# CONNECT.net
KiCad netlist of a schematic drawn in Altium Designer
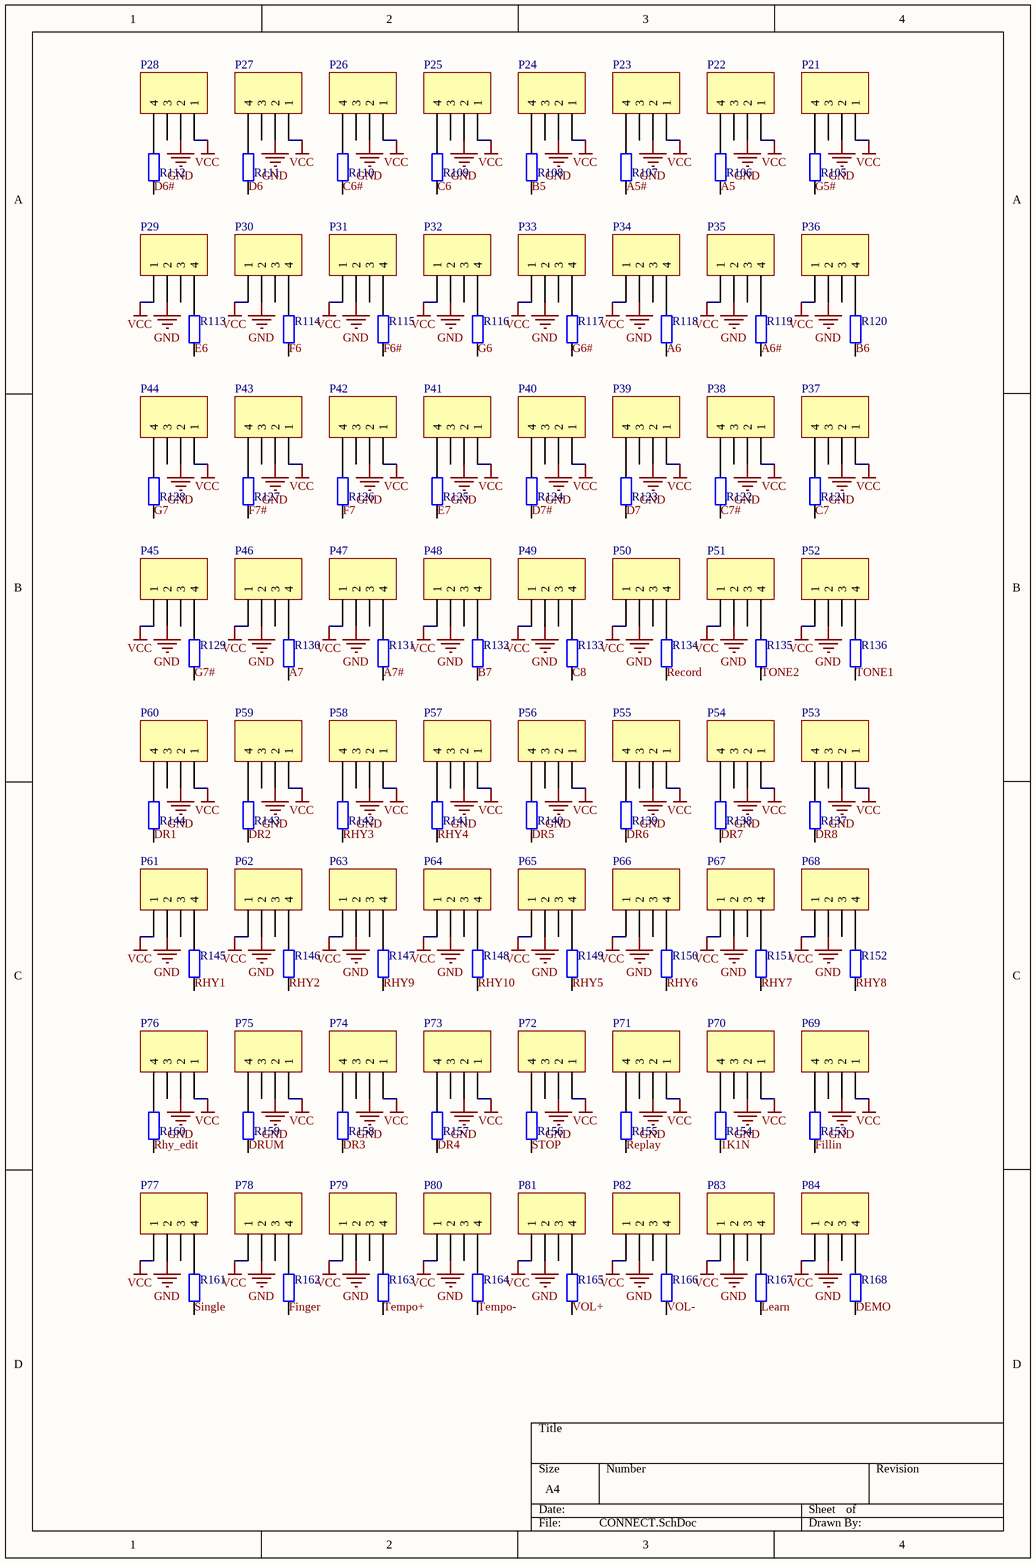
[diagram p0: CONNECT.SchDoc]

(export (version "E")
  (design (tool "Eeschema 10.0.6"))
  (components
    (comp (ref "P21")
      (value "Header 4")
      (footprint "FPC1.0-2H-WS-4P")
      (description "Header, 4-Pin")
      (fields (field (name "PUBLISHER") "Altium Limited"))
      (libsource (lib "") (part "Header 4_1"))
    )
    (comp (ref "P22")
      (value "Header 4")
      (footprint "FPC1.0-2H-WS-4P")
      (description "Header, 4-Pin")
      (fields (field (name "PUBLISHER") "Altium Limited"))
      (libsource (lib "") (part "Header 4_1"))
    )
    (comp (ref "P23")
      (value "Header 4")
      (footprint "FPC1.0-2H-WS-4P")
      (description "Header, 4-Pin")
      (fields (field (name "PUBLISHER") "Altium Limited"))
      (libsource (lib "") (part "Header 4_1"))
    )
    (comp (ref "P24")
      (value "Header 4")
      (footprint "FPC1.0-2H-WS-4P")
      (description "Header, 4-Pin")
      (fields (field (name "PUBLISHER") "Altium Limited"))
      (libsource (lib "") (part "Header 4_1"))
    )
    (comp (ref "P25")
      (value "Header 4")
      (footprint "FPC1.0-2H-WS-4P")
      (description "Header, 4-Pin")
      (fields (field (name "PUBLISHER") "Altium Limited"))
      (libsource (lib "") (part "Header 4_1"))
    )
    (comp (ref "P26")
      (value "Header 4")
      (footprint "FPC1.0-2H-WS-4P")
      (description "Header, 4-Pin")
      (fields (field (name "PUBLISHER") "Altium Limited"))
      (libsource (lib "") (part "Header 4_1"))
    )
    (comp (ref "P27")
      (value "Header 4")
      (footprint "FPC1.0-2H-WS-4P")
      (description "Header, 4-Pin")
      (fields (field (name "PUBLISHER") "Altium Limited"))
      (libsource (lib "") (part "Header 4_1"))
    )
    (comp (ref "P28")
      (value "Header 4")
      (footprint "FPC1.0-2H-WS-4P")
      (description "Header, 4-Pin")
      (fields (field (name "PUBLISHER") "Altium Limited"))
      (libsource (lib "") (part "Header 4_1"))
    )
    (comp (ref "P29")
      (value "Header 4")
      (footprint "FPC1.0-2H-WS-4P")
      (description "Header, 4-Pin")
      (fields (field (name "PUBLISHER") "Altium Limited"))
      (libsource (lib "Miscellaneous Connectors") (part "Header 4"))
    )
    (comp (ref "P30")
      (value "Header 4")
      (footprint "FPC1.0-2H-WS-4P")
      (description "Header, 4-Pin")
      (fields (field (name "PUBLISHER") "Altium Limited"))
      (libsource (lib "Miscellaneous Connectors") (part "Header 4"))
    )
    (comp (ref "P31")
      (value "Header 4")
      (footprint "FPC1.0-2H-WS-4P")
      (description "Header, 4-Pin")
      (fields (field (name "PUBLISHER") "Altium Limited"))
      (libsource (lib "Miscellaneous Connectors") (part "Header 4"))
    )
    (comp (ref "P32")
      (value "Header 4")
      (footprint "FPC1.0-2H-WS-4P")
      (description "Header, 4-Pin")
      (fields (field (name "PUBLISHER") "Altium Limited"))
      (libsource (lib "Miscellaneous Connectors") (part "Header 4"))
    )
    (comp (ref "P33")
      (value "Header 4")
      (footprint "FPC1.0-2H-WS-4P")
      (description "Header, 4-Pin")
      (fields (field (name "PUBLISHER") "Altium Limited"))
      (libsource (lib "Miscellaneous Connectors") (part "Header 4"))
    )
    (comp (ref "P34")
      (value "Header 4")
      (footprint "FPC1.0-2H-WS-4P")
      (description "Header, 4-Pin")
      (fields (field (name "PUBLISHER") "Altium Limited"))
      (libsource (lib "Miscellaneous Connectors") (part "Header 4"))
    )
    (comp (ref "P35")
      (value "Header 4")
      (footprint "FPC1.0-2H-WS-4P")
      (description "Header, 4-Pin")
      (fields (field (name "PUBLISHER") "Altium Limited"))
      (libsource (lib "Miscellaneous Connectors") (part "Header 4"))
    )
    (comp (ref "P36")
      (value "Header 4")
      (footprint "FPC1.0-2H-WS-4P")
      (description "Header, 4-Pin")
      (fields (field (name "PUBLISHER") "Altium Limited"))
      (libsource (lib "Miscellaneous Connectors") (part "Header 4"))
    )
    (comp (ref "P37")
      (value "Header 4")
      (footprint "FPC1.0-2H-WS-4P")
      (description "Header, 4-Pin")
      (fields (field (name "PUBLISHER") "Altium Limited"))
      (libsource (lib "") (part "Header 4_1"))
    )
    (comp (ref "P38")
      (value "Header 4")
      (footprint "FPC1.0-2H-WS-4P")
      (description "Header, 4-Pin")
      (fields (field (name "PUBLISHER") "Altium Limited"))
      (libsource (lib "") (part "Header 4_1"))
    )
    (comp (ref "P39")
      (value "Header 4")
      (footprint "FPC1.0-2H-WS-4P")
      (description "Header, 4-Pin")
      (fields (field (name "PUBLISHER") "Altium Limited"))
      (libsource (lib "") (part "Header 4_1"))
    )
    (comp (ref "P40")
      (value "Header 4")
      (footprint "FPC1.0-2H-WS-4P")
      (description "Header, 4-Pin")
      (fields (field (name "PUBLISHER") "Altium Limited"))
      (libsource (lib "") (part "Header 4_1"))
    )
    (comp (ref "P41")
      (value "Header 4")
      (footprint "FPC1.0-2H-WS-4P")
      (description "Header, 4-Pin")
      (fields (field (name "PUBLISHER") "Altium Limited"))
      (libsource (lib "") (part "Header 4_1"))
    )
    (comp (ref "P42")
      (value "Header 4")
      (footprint "FPC1.0-2H-WS-4P")
      (description "Header, 4-Pin")
      (fields (field (name "PUBLISHER") "Altium Limited"))
      (libsource (lib "") (part "Header 4_1"))
    )
    (comp (ref "P43")
      (value "Header 4")
      (footprint "FPC1.0-2H-WS-4P")
      (description "Header, 4-Pin")
      (fields (field (name "PUBLISHER") "Altium Limited"))
      (libsource (lib "") (part "Header 4_1"))
    )
    (comp (ref "P44")
      (value "Header 4")
      (footprint "FPC1.0-2H-WS-4P")
      (description "Header, 4-Pin")
      (fields (field (name "PUBLISHER") "Altium Limited"))
      (libsource (lib "") (part "Header 4_1"))
    )
    (comp (ref "P45")
      (value "Header 4")
      (footprint "FPC1.0-2H-WS-4P")
      (description "Header, 4-Pin")
      (fields (field (name "PUBLISHER") "Altium Limited"))
      (libsource (lib "Miscellaneous Connectors") (part "Header 4"))
    )
    (comp (ref "P46")
      (value "Header 4")
      (footprint "FPC1.0-2H-WS-4P")
      (description "Header, 4-Pin")
      (fields (field (name "PUBLISHER") "Altium Limited"))
      (libsource (lib "Miscellaneous Connectors") (part "Header 4"))
    )
    (comp (ref "P47")
      (value "Header 4")
      (footprint "FPC1.0-2H-WS-4P")
      (description "Header, 4-Pin")
      (fields (field (name "PUBLISHER") "Altium Limited"))
      (libsource (lib "Miscellaneous Connectors") (part "Header 4"))
    )
    (comp (ref "P48")
      (value "Header 4")
      (footprint "FPC1.0-2H-WS-4P")
      (description "Header, 4-Pin")
      (fields (field (name "PUBLISHER") "Altium Limited"))
      (libsource (lib "Miscellaneous Connectors") (part "Header 4"))
    )
    (comp (ref "P49")
      (value "Header 4")
      (footprint "FPC1.0-2H-WS-4P")
      (description "Header, 4-Pin")
      (fields (field (name "PUBLISHER") "Altium Limited"))
      (libsource (lib "Miscellaneous Connectors") (part "Header 4"))
    )
    (comp (ref "P50")
      (value "Header 4")
      (footprint "FPC1.0-2H-WS-4P")
      (description "Header, 4-Pin")
      (fields (field (name "PUBLISHER") "Altium Limited"))
      (libsource (lib "Miscellaneous Connectors") (part "Header 4"))
    )
    (comp (ref "P51")
      (value "Header 4")
      (footprint "FPC1.0-2H-WS-4P")
      (description "Header, 4-Pin")
      (fields (field (name "PUBLISHER") "Altium Limited"))
      (libsource (lib "Miscellaneous Connectors") (part "Header 4"))
    )
    (comp (ref "P52")
      (value "Header 4")
      (footprint "FPC1.0-2H-WS-4P")
      (description "Header, 4-Pin")
      (fields (field (name "PUBLISHER") "Altium Limited"))
      (libsource (lib "Miscellaneous Connectors") (part "Header 4"))
    )
    (comp (ref "P53")
      (value "Header 4")
      (footprint "FPC1.0-2H-WS-4P")
      (description "Header, 4-Pin")
      (fields (field (name "PUBLISHER") "Altium Limited"))
      (libsource (lib "") (part "Header 4_1"))
    )
    (comp (ref "P54")
      (value "Header 4")
      (footprint "FPC1.0-2H-WS-4P")
      (description "Header, 4-Pin")
      (fields (field (name "PUBLISHER") "Altium Limited"))
      (libsource (lib "") (part "Header 4_1"))
    )
    (comp (ref "P55")
      (value "Header 4")
      (footprint "FPC1.0-2H-WS-4P")
      (description "Header, 4-Pin")
      (fields (field (name "PUBLISHER") "Altium Limited"))
      (libsource (lib "") (part "Header 4_1"))
    )
    (comp (ref "P56")
      (value "Header 4")
      (footprint "FPC1.0-2H-WS-4P")
      (description "Header, 4-Pin")
      (fields (field (name "PUBLISHER") "Altium Limited"))
      (libsource (lib "") (part "Header 4_1"))
    )
    (comp (ref "P57")
      (value "Header 4")
      (footprint "FPC1.0-2H-WS-4P")
      (description "Header, 4-Pin")
      (fields (field (name "PUBLISHER") "Altium Limited"))
      (libsource (lib "") (part "Header 4_1"))
    )
    (comp (ref "P58")
      (value "Header 4")
      (footprint "FPC1.0-2H-WS-4P")
      (description "Header, 4-Pin")
      (fields (field (name "PUBLISHER") "Altium Limited"))
      (libsource (lib "") (part "Header 4_1"))
    )
    (comp (ref "P59")
      (value "Header 4")
      (footprint "FPC1.0-2H-WS-4P")
      (description "Header, 4-Pin")
      (fields (field (name "PUBLISHER") "Altium Limited"))
      (libsource (lib "") (part "Header 4_1"))
    )
    (comp (ref "P60")
      (value "Header 4")
      (footprint "FPC1.0-2H-WS-4P")
      (description "Header, 4-Pin")
      (fields (field (name "PUBLISHER") "Altium Limited"))
      (libsource (lib "") (part "Header 4_1"))
    )
    (comp (ref "P61")
      (value "Header 4")
      (footprint "FPC1.0-2H-WS-4P")
      (description "Header, 4-Pin")
      (fields (field (name "PUBLISHER") "Altium Limited"))
      (libsource (lib "Miscellaneous Connectors") (part "Header 4"))
    )
    (comp (ref "P62")
      (value "Header 4")
      (footprint "FPC1.0-2H-WS-4P")
      (description "Header, 4-Pin")
      (fields (field (name "PUBLISHER") "Altium Limited"))
      (libsource (lib "Miscellaneous Connectors") (part "Header 4"))
    )
    (comp (ref "P63")
      (value "Header 4")
      (footprint "FPC1.0-2H-WS-4P")
      (description "Header, 4-Pin")
      (fields (field (name "PUBLISHER") "Altium Limited"))
      (libsource (lib "Miscellaneous Connectors") (part "Header 4"))
    )
    (comp (ref "P64")
      (value "Header 4")
      (footprint "FPC1.0-2H-WS-4P")
      (description "Header, 4-Pin")
      (fields (field (name "PUBLISHER") "Altium Limited"))
      (libsource (lib "Miscellaneous Connectors") (part "Header 4"))
    )
    (comp (ref "P65")
      (value "Header 4")
      (footprint "FPC1.0-2H-WS-4P")
      (description "Header, 4-Pin")
      (fields (field (name "PUBLISHER") "Altium Limited"))
      (libsource (lib "Miscellaneous Connectors") (part "Header 4"))
    )
    (comp (ref "P66")
      (value "Header 4")
      (footprint "FPC1.0-2H-WS-4P")
      (description "Header, 4-Pin")
      (fields (field (name "PUBLISHER") "Altium Limited"))
      (libsource (lib "Miscellaneous Connectors") (part "Header 4"))
    )
    (comp (ref "P67")
      (value "Header 4")
      (footprint "FPC1.0-2H-WS-4P")
      (description "Header, 4-Pin")
      (fields (field (name "PUBLISHER") "Altium Limited"))
      (libsource (lib "Miscellaneous Connectors") (part "Header 4"))
    )
    (comp (ref "P68")
      (value "Header 4")
      (footprint "FPC1.0-2H-WS-4P")
      (description "Header, 4-Pin")
      (fields (field (name "PUBLISHER") "Altium Limited"))
      (libsource (lib "Miscellaneous Connectors") (part "Header 4"))
    )
    (comp (ref "P69")
      (value "Header 4")
      (footprint "FPC1.0-2H-WS-4P")
      (description "Header, 4-Pin")
      (fields (field (name "PUBLISHER") "Altium Limited"))
      (libsource (lib "") (part "Header 4_1"))
    )
    (comp (ref "P70")
      (value "Header 4")
      (footprint "FPC1.0-2H-WS-4P")
      (description "Header, 4-Pin")
      (fields (field (name "PUBLISHER") "Altium Limited"))
      (libsource (lib "") (part "Header 4_1"))
    )
    (comp (ref "P71")
      (value "Header 4")
      (footprint "FPC1.0-2H-WS-4P")
      (description "Header, 4-Pin")
      (fields (field (name "PUBLISHER") "Altium Limited"))
      (libsource (lib "") (part "Header 4_1"))
    )
    (comp (ref "P72")
      (value "Header 4")
      (footprint "FPC1.0-2H-WS-4P")
      (description "Header, 4-Pin")
      (fields (field (name "PUBLISHER") "Altium Limited"))
      (libsource (lib "") (part "Header 4_1"))
    )
    (comp (ref "P73")
      (value "Header 4")
      (footprint "FPC1.0-2H-WS-4P")
      (description "Header, 4-Pin")
      (fields (field (name "PUBLISHER") "Altium Limited"))
      (libsource (lib "") (part "Header 4_1"))
    )
    (comp (ref "P74")
      (value "Header 4")
      (footprint "FPC1.0-2H-WS-4P")
      (description "Header, 4-Pin")
      (fields (field (name "PUBLISHER") "Altium Limited"))
      (libsource (lib "") (part "Header 4_1"))
    )
    (comp (ref "P75")
      (value "Header 4")
      (footprint "FPC1.0-2H-WS-4P")
      (description "Header, 4-Pin")
      (fields (field (name "PUBLISHER") "Altium Limited"))
      (libsource (lib "") (part "Header 4_1"))
    )
    (comp (ref "P76")
      (value "Header 4")
      (footprint "FPC1.0-2H-WS-4P")
      (description "Header, 4-Pin")
      (fields (field (name "PUBLISHER") "Altium Limited"))
      (libsource (lib "") (part "Header 4_1"))
    )
    (comp (ref "P77")
      (value "Header 4")
      (footprint "FPC1.0-2H-WS-4P")
      (description "Header, 4-Pin")
      (fields (field (name "PUBLISHER") "Altium Limited"))
      (libsource (lib "Miscellaneous Connectors") (part "Header 4"))
    )
    (comp (ref "P78")
      (value "Header 4")
      (footprint "FPC1.0-2H-WS-4P")
      (description "Header, 4-Pin")
      (fields (field (name "PUBLISHER") "Altium Limited"))
      (libsource (lib "Miscellaneous Connectors") (part "Header 4"))
    )
    (comp (ref "P79")
      (value "Header 4")
      (footprint "FPC1.0-2H-WS-4P")
      (description "Header, 4-Pin")
      (fields (field (name "PUBLISHER") "Altium Limited"))
      (libsource (lib "Miscellaneous Connectors") (part "Header 4"))
    )
    (comp (ref "P80")
      (value "Header 4")
      (footprint "FPC1.0-2H-WS-4P")
      (description "Header, 4-Pin")
      (fields (field (name "PUBLISHER") "Altium Limited"))
      (libsource (lib "Miscellaneous Connectors") (part "Header 4"))
    )
    (comp (ref "P81")
      (value "Header 4")
      (footprint "FPC1.0-2H-WS-4P")
      (description "Header, 4-Pin")
      (fields (field (name "PUBLISHER") "Altium Limited"))
      (libsource (lib "Miscellaneous Connectors") (part "Header 4"))
    )
    (comp (ref "P82")
      (value "Header 4")
      (footprint "FPC1.0-2H-WS-4P")
      (description "Header, 4-Pin")
      (fields (field (name "PUBLISHER") "Altium Limited"))
      (libsource (lib "Miscellaneous Connectors") (part "Header 4"))
    )
    (comp (ref "P83")
      (value "Header 4")
      (footprint "FPC1.0-2H-WS-4P")
      (description "Header, 4-Pin")
      (fields (field (name "PUBLISHER") "Altium Limited"))
      (libsource (lib "Miscellaneous Connectors") (part "Header 4"))
    )
    (comp (ref "P84")
      (value "Header 4")
      (footprint "FPC1.0-2H-WS-4P")
      (description "Header, 4-Pin")
      (fields (field (name "PUBLISHER") "Altium Limited"))
      (libsource (lib "Miscellaneous Connectors") (part "Header 4"))
    )
    (comp (ref "R105")
      (value "1KΩ (1001) ±1%")
      (footprint "0603_R")
      (description "贴片电阻")
      (libsource (lib "Miscellaneous Devices LC") (part "0603 1KΩ (1001) 1%"))
    )
    (comp (ref "R106")
      (value "1KΩ (1001) ±1%")
      (footprint "0603_R")
      (description "贴片电阻")
      (libsource (lib "Miscellaneous Devices LC") (part "0603 1KΩ (1001) 1%"))
    )
    (comp (ref "R107")
      (value "1KΩ (1001) ±1%")
      (footprint "0603_R")
      (description "贴片电阻")
      (libsource (lib "Miscellaneous Devices LC") (part "0603 1KΩ (1001) 1%"))
    )
    (comp (ref "R108")
      (value "1KΩ (1001) ±1%")
      (footprint "0603_R")
      (description "贴片电阻")
      (libsource (lib "Miscellaneous Devices LC") (part "0603 1KΩ (1001) 1%"))
    )
    (comp (ref "R109")
      (value "1KΩ (1001) ±1%")
      (footprint "0603_R")
      (description "贴片电阻")
      (libsource (lib "Miscellaneous Devices LC") (part "0603 1KΩ (1001) 1%"))
    )
    (comp (ref "R110")
      (value "1KΩ (1001) ±1%")
      (footprint "0603_R")
      (description "贴片电阻")
      (libsource (lib "Miscellaneous Devices LC") (part "0603 1KΩ (1001) 1%"))
    )
    (comp (ref "R111")
      (value "1KΩ (1001) ±1%")
      (footprint "0603_R")
      (description "贴片电阻")
      (libsource (lib "Miscellaneous Devices LC") (part "0603 1KΩ (1001) 1%"))
    )
    (comp (ref "R112")
      (value "1KΩ (1001) ±1%")
      (footprint "0603_R")
      (description "贴片电阻")
      (libsource (lib "Miscellaneous Devices LC") (part "0603 1KΩ (1001) 1%"))
    )
    (comp (ref "R113")
      (value "1KΩ (1001) ±1%")
      (footprint "0603_R")
      (description "贴片电阻")
      (libsource (lib "") (part "0603 1KΩ (1001) 1%_1"))
    )
    (comp (ref "R114")
      (value "1KΩ (1001) ±1%")
      (footprint "0603_R")
      (description "贴片电阻")
      (libsource (lib "") (part "0603 1KΩ (1001) 1%_1"))
    )
    (comp (ref "R115")
      (value "1KΩ (1001) ±1%")
      (footprint "0603_R")
      (description "贴片电阻")
      (libsource (lib "") (part "0603 1KΩ (1001) 1%_1"))
    )
    (comp (ref "R116")
      (value "1KΩ (1001) ±1%")
      (footprint "0603_R")
      (description "贴片电阻")
      (libsource (lib "") (part "0603 1KΩ (1001) 1%_1"))
    )
    (comp (ref "R117")
      (value "1KΩ (1001) ±1%")
      (footprint "0603_R")
      (description "贴片电阻")
      (libsource (lib "") (part "0603 1KΩ (1001) 1%_1"))
    )
    (comp (ref "R118")
      (value "1KΩ (1001) ±1%")
      (footprint "0603_R")
      (description "贴片电阻")
      (libsource (lib "") (part "0603 1KΩ (1001) 1%_1"))
    )
    (comp (ref "R119")
      (value "1KΩ (1001) ±1%")
      (footprint "0603_R")
      (description "贴片电阻")
      (libsource (lib "") (part "0603 1KΩ (1001) 1%_1"))
    )
    (comp (ref "R120")
      (value "1KΩ (1001) ±1%")
      (footprint "0603_R")
      (description "贴片电阻")
      (libsource (lib "") (part "0603 1KΩ (1001) 1%_1"))
    )
    (comp (ref "R121")
      (value "1KΩ (1001) ±1%")
      (footprint "0603_R")
      (description "贴片电阻")
      (libsource (lib "Miscellaneous Devices LC") (part "0603 1KΩ (1001) 1%"))
    )
    (comp (ref "R122")
      (value "1KΩ (1001) ±1%")
      (footprint "0603_R")
      (description "贴片电阻")
      (libsource (lib "Miscellaneous Devices LC") (part "0603 1KΩ (1001) 1%"))
    )
    (comp (ref "R123")
      (value "1KΩ (1001) ±1%")
      (footprint "0603_R")
      (description "贴片电阻")
      (libsource (lib "Miscellaneous Devices LC") (part "0603 1KΩ (1001) 1%"))
    )
    (comp (ref "R124")
      (value "1KΩ (1001) ±1%")
      (footprint "0603_R")
      (description "贴片电阻")
      (libsource (lib "Miscellaneous Devices LC") (part "0603 1KΩ (1001) 1%"))
    )
    (comp (ref "R125")
      (value "1KΩ (1001) ±1%")
      (footprint "0603_R")
      (description "贴片电阻")
      (libsource (lib "Miscellaneous Devices LC") (part "0603 1KΩ (1001) 1%"))
    )
    (comp (ref "R126")
      (value "1KΩ (1001) ±1%")
      (footprint "0603_R")
      (description "贴片电阻")
      (libsource (lib "Miscellaneous Devices LC") (part "0603 1KΩ (1001) 1%"))
    )
    (comp (ref "R127")
      (value "1KΩ (1001) ±1%")
      (footprint "0603_R")
      (description "贴片电阻")
      (libsource (lib "Miscellaneous Devices LC") (part "0603 1KΩ (1001) 1%"))
    )
    (comp (ref "R128")
      (value "1KΩ (1001) ±1%")
      (footprint "0603_R")
      (description "贴片电阻")
      (libsource (lib "Miscellaneous Devices LC") (part "0603 1KΩ (1001) 1%"))
    )
    (comp (ref "R129")
      (value "1KΩ (1001) ±1%")
      (footprint "0603_R")
      (description "贴片电阻")
      (libsource (lib "") (part "0603 1KΩ (1001) 1%_1"))
    )
    (comp (ref "R130")
      (value "1KΩ (1001) ±1%")
      (footprint "0603_R")
      (description "贴片电阻")
      (libsource (lib "") (part "0603 1KΩ (1001) 1%_1"))
    )
    (comp (ref "R131")
      (value "1KΩ (1001) ±1%")
      (footprint "0603_R")
      (description "贴片电阻")
      (libsource (lib "") (part "0603 1KΩ (1001) 1%_1"))
    )
    (comp (ref "R132")
      (value "1KΩ (1001) ±1%")
      (footprint "0603_R")
      (description "贴片电阻")
      (libsource (lib "") (part "0603 1KΩ (1001) 1%_1"))
    )
    (comp (ref "R133")
      (value "1KΩ (1001) ±1%")
      (footprint "0603_R")
      (description "贴片电阻")
      (libsource (lib "") (part "0603 1KΩ (1001) 1%_1"))
    )
    (comp (ref "R134")
      (value "1KΩ (1001) ±1%")
      (footprint "0603_R")
      (description "贴片电阻")
      (libsource (lib "") (part "0603 1KΩ (1001) 1%_1"))
    )
    (comp (ref "R135")
      (value "1KΩ (1001) ±1%")
      (footprint "0603_R")
      (description "贴片电阻")
      (libsource (lib "") (part "0603 1KΩ (1001) 1%_1"))
    )
    (comp (ref "R136")
      (value "1KΩ (1001) ±1%")
      (footprint "0603_R")
      (description "贴片电阻")
      (libsource (lib "") (part "0603 1KΩ (1001) 1%_1"))
    )
    (comp (ref "R137")
      (value "1KΩ (1001) ±1%")
      (footprint "0603_R")
      (description "贴片电阻")
      (libsource (lib "Miscellaneous Devices LC") (part "0603 1KΩ (1001) 1%"))
    )
    (comp (ref "R138")
      (value "1KΩ (1001) ±1%")
      (footprint "0603_R")
      (description "贴片电阻")
      (libsource (lib "Miscellaneous Devices LC") (part "0603 1KΩ (1001) 1%"))
    )
    (comp (ref "R139")
      (value "1KΩ (1001) ±1%")
      (footprint "0603_R")
      (description "贴片电阻")
      (libsource (lib "Miscellaneous Devices LC") (part "0603 1KΩ (1001) 1%"))
    )
    (comp (ref "R140")
      (value "1KΩ (1001) ±1%")
      (footprint "0603_R")
      (description "贴片电阻")
      (libsource (lib "Miscellaneous Devices LC") (part "0603 1KΩ (1001) 1%"))
    )
    (comp (ref "R141")
      (value "1KΩ (1001) ±1%")
      (footprint "0603_R")
      (description "贴片电阻")
      (libsource (lib "Miscellaneous Devices LC") (part "0603 1KΩ (1001) 1%"))
    )
    (comp (ref "R142")
      (value "1KΩ (1001) ±1%")
      (footprint "0603_R")
      (description "贴片电阻")
      (libsource (lib "Miscellaneous Devices LC") (part "0603 1KΩ (1001) 1%"))
    )
    (comp (ref "R143")
      (value "1KΩ (1001) ±1%")
      (footprint "0603_R")
      (description "贴片电阻")
      (libsource (lib "Miscellaneous Devices LC") (part "0603 1KΩ (1001) 1%"))
    )
    (comp (ref "R144")
      (value "1KΩ (1001) ±1%")
      (footprint "0603_R")
      (description "贴片电阻")
      (libsource (lib "Miscellaneous Devices LC") (part "0603 1KΩ (1001) 1%"))
    )
    (comp (ref "R145")
      (value "1KΩ (1001) ±1%")
      (footprint "0603_R")
      (description "贴片电阻")
      (libsource (lib "") (part "0603 1KΩ (1001) 1%_1"))
    )
    (comp (ref "R146")
      (value "1KΩ (1001) ±1%")
      (footprint "0603_R")
      (description "贴片电阻")
      (libsource (lib "") (part "0603 1KΩ (1001) 1%_1"))
    )
    (comp (ref "R147")
      (value "1KΩ (1001) ±1%")
      (footprint "0603_R")
      (description "贴片电阻")
      (libsource (lib "") (part "0603 1KΩ (1001) 1%_1"))
    )
    (comp (ref "R148")
      (value "1KΩ (1001) ±1%")
      (footprint "0603_R")
      (description "贴片电阻")
      (libsource (lib "") (part "0603 1KΩ (1001) 1%_1"))
    )
    (comp (ref "R149")
      (value "1KΩ (1001) ±1%")
      (footprint "0603_R")
      (description "贴片电阻")
      (libsource (lib "") (part "0603 1KΩ (1001) 1%_1"))
    )
    (comp (ref "R150")
      (value "1KΩ (1001) ±1%")
      (footprint "0603_R")
      (description "贴片电阻")
      (libsource (lib "") (part "0603 1KΩ (1001) 1%_1"))
    )
    (comp (ref "R151")
      (value "1KΩ (1001) ±1%")
      (footprint "0603_R")
      (description "贴片电阻")
      (libsource (lib "") (part "0603 1KΩ (1001) 1%_1"))
    )
    (comp (ref "R152")
      (value "1KΩ (1001) ±1%")
      (footprint "0603_R")
      (description "贴片电阻")
      (libsource (lib "") (part "0603 1KΩ (1001) 1%_1"))
    )
    (comp (ref "R153")
      (value "1KΩ (1001) ±1%")
      (footprint "0603_R")
      (description "贴片电阻")
      (libsource (lib "Miscellaneous Devices LC") (part "0603 1KΩ (1001) 1%"))
    )
    (comp (ref "R154")
      (value "1KΩ (1001) ±1%")
      (footprint "0603_R")
      (description "贴片电阻")
      (libsource (lib "Miscellaneous Devices LC") (part "0603 1KΩ (1001) 1%"))
    )
    (comp (ref "R155")
      (value "1KΩ (1001) ±1%")
      (footprint "0603_R")
      (description "贴片电阻")
      (libsource (lib "Miscellaneous Devices LC") (part "0603 1KΩ (1001) 1%"))
    )
    (comp (ref "R156")
      (value "1KΩ (1001) ±1%")
      (footprint "0603_R")
      (description "贴片电阻")
      (libsource (lib "Miscellaneous Devices LC") (part "0603 1KΩ (1001) 1%"))
    )
    (comp (ref "R157")
      (value "1KΩ (1001) ±1%")
      (footprint "0603_R")
      (description "贴片电阻")
      (libsource (lib "Miscellaneous Devices LC") (part "0603 1KΩ (1001) 1%"))
    )
    (comp (ref "R158")
      (value "1KΩ (1001) ±1%")
      (footprint "0603_R")
      (description "贴片电阻")
      (libsource (lib "Miscellaneous Devices LC") (part "0603 1KΩ (1001) 1%"))
    )
    (comp (ref "R159")
      (value "1KΩ (1001) ±1%")
      (footprint "0603_R")
      (description "贴片电阻")
      (libsource (lib "Miscellaneous Devices LC") (part "0603 1KΩ (1001) 1%"))
    )
    (comp (ref "R160")
      (value "1KΩ (1001) ±1%")
      (footprint "0603_R")
      (description "贴片电阻")
      (libsource (lib "Miscellaneous Devices LC") (part "0603 1KΩ (1001) 1%"))
    )
    (comp (ref "R161")
      (value "1KΩ (1001) ±1%")
      (footprint "0603_R")
      (description "贴片电阻")
      (libsource (lib "") (part "0603 1KΩ (1001) 1%_1"))
    )
    (comp (ref "R162")
      (value "1KΩ (1001) ±1%")
      (footprint "0603_R")
      (description "贴片电阻")
      (libsource (lib "") (part "0603 1KΩ (1001) 1%_1"))
    )
    (comp (ref "R163")
      (value "1KΩ (1001) ±1%")
      (footprint "0603_R")
      (description "贴片电阻")
      (libsource (lib "") (part "0603 1KΩ (1001) 1%_1"))
    )
    (comp (ref "R164")
      (value "1KΩ (1001) ±1%")
      (footprint "0603_R")
      (description "贴片电阻")
      (libsource (lib "") (part "0603 1KΩ (1001) 1%_1"))
    )
    (comp (ref "R165")
      (value "1KΩ (1001) ±1%")
      (footprint "0603_R")
      (description "贴片电阻")
      (libsource (lib "") (part "0603 1KΩ (1001) 1%_1"))
    )
    (comp (ref "R166")
      (value "1KΩ (1001) ±1%")
      (footprint "0603_R")
      (description "贴片电阻")
      (libsource (lib "") (part "0603 1KΩ (1001) 1%_1"))
    )
    (comp (ref "R167")
      (value "1KΩ (1001) ±1%")
      (footprint "0603_R")
      (description "贴片电阻")
      (libsource (lib "") (part "0603 1KΩ (1001) 1%_1"))
    )
    (comp (ref "R168")
      (value "1KΩ (1001) ±1%")
      (footprint "0603_R")
      (description "贴片电阻")
      (libsource (lib "") (part "0603 1KΩ (1001) 1%_1"))
    )
  )
  (nets
    (net (code "1") (name "/1K1N") (class "Default")
      (node (ref "R154") (pin "1") (pinfunction "1_1") (pintype "passive"))
    )
    (net (code "2") (name "/A5") (class "Default")
      (node (ref "R106") (pin "1") (pinfunction "1_1") (pintype "passive"))
    )
    (net (code "3") (name "/A5#") (class "Default")
      (node (ref "R107") (pin "1") (pinfunction "1_1") (pintype "passive"))
    )
    (net (code "4") (name "/A6") (class "Default")
      (node (ref "R118") (pin "1") (pinfunction "1_1") (pintype "passive"))
    )
    (net (code "5") (name "/A6#") (class "Default")
      (node (ref "R119") (pin "1") (pinfunction "1_1") (pintype "passive"))
    )
    (net (code "6") (name "/A7") (class "Default")
      (node (ref "R130") (pin "1") (pinfunction "1_1") (pintype "passive"))
    )
    (net (code "7") (name "/A7#") (class "Default")
      (node (ref "R131") (pin "1") (pinfunction "1_1") (pintype "passive"))
    )
    (net (code "8") (name "/B5") (class "Default")
      (node (ref "R108") (pin "1") (pinfunction "1_1") (pintype "passive"))
    )
    (net (code "9") (name "/B6") (class "Default")
      (node (ref "R120") (pin "1") (pinfunction "1_1") (pintype "passive"))
    )
    (net (code "10") (name "/B7") (class "Default")
      (node (ref "R132") (pin "1") (pinfunction "1_1") (pintype "passive"))
    )
    (net (code "11") (name "/C6") (class "Default")
      (node (ref "R109") (pin "1") (pinfunction "1_1") (pintype "passive"))
    )
    (net (code "12") (name "/C6#") (class "Default")
      (node (ref "R110") (pin "1") (pinfunction "1_1") (pintype "passive"))
    )
    (net (code "13") (name "/C7") (class "Default")
      (node (ref "R121") (pin "1") (pinfunction "1_1") (pintype "passive"))
    )
    (net (code "14") (name "/C7#") (class "Default")
      (node (ref "R122") (pin "1") (pinfunction "1_1") (pintype "passive"))
    )
    (net (code "15") (name "/C8") (class "Default")
      (node (ref "R133") (pin "1") (pinfunction "1_1") (pintype "passive"))
    )
    (net (code "16") (name "/D6") (class "Default")
      (node (ref "R111") (pin "1") (pinfunction "1_1") (pintype "passive"))
    )
    (net (code "17") (name "/D6#") (class "Default")
      (node (ref "R112") (pin "1") (pinfunction "1_1") (pintype "passive"))
    )
    (net (code "18") (name "/D7") (class "Default")
      (node (ref "R123") (pin "1") (pinfunction "1_1") (pintype "passive"))
    )
    (net (code "19") (name "/D7#") (class "Default")
      (node (ref "R124") (pin "1") (pinfunction "1_1") (pintype "passive"))
    )
    (net (code "20") (name "/DEMO") (class "Default")
      (node (ref "R168") (pin "1") (pinfunction "1_1") (pintype "passive"))
    )
    (net (code "21") (name "/DR1") (class "Default")
      (node (ref "R144") (pin "1") (pinfunction "1_1") (pintype "passive"))
    )
    (net (code "22") (name "/DR2") (class "Default")
      (node (ref "R143") (pin "1") (pinfunction "1_1") (pintype "passive"))
    )
    (net (code "23") (name "/DR3") (class "Default")
      (node (ref "R158") (pin "1") (pinfunction "1_1") (pintype "passive"))
    )
    (net (code "24") (name "/DR4") (class "Default")
      (node (ref "R157") (pin "1") (pinfunction "1_1") (pintype "passive"))
    )
    (net (code "25") (name "/DR5") (class "Default")
      (node (ref "R140") (pin "1") (pinfunction "1_1") (pintype "passive"))
    )
    (net (code "26") (name "/DR6") (class "Default")
      (node (ref "R139") (pin "1") (pinfunction "1_1") (pintype "passive"))
    )
    (net (code "27") (name "/DR7") (class "Default")
      (node (ref "R138") (pin "1") (pinfunction "1_1") (pintype "passive"))
    )
    (net (code "28") (name "/DR8") (class "Default")
      (node (ref "R137") (pin "1") (pinfunction "1_1") (pintype "passive"))
    )
    (net (code "29") (name "/DRUM") (class "Default")
      (node (ref "R159") (pin "1") (pinfunction "1_1") (pintype "passive"))
    )
    (net (code "30") (name "/E6") (class "Default")
      (node (ref "R113") (pin "1") (pinfunction "1_1") (pintype "passive"))
    )
    (net (code "31") (name "/E7") (class "Default")
      (node (ref "R125") (pin "1") (pinfunction "1_1") (pintype "passive"))
    )
    (net (code "32") (name "/F6") (class "Default")
      (node (ref "R114") (pin "1") (pinfunction "1_1") (pintype "passive"))
    )
    (net (code "33") (name "/F6#") (class "Default")
      (node (ref "R115") (pin "1") (pinfunction "1_1") (pintype "passive"))
    )
    (net (code "34") (name "/F7") (class "Default")
      (node (ref "R126") (pin "1") (pinfunction "1_1") (pintype "passive"))
    )
    (net (code "35") (name "/F7#") (class "Default")
      (node (ref "R127") (pin "1") (pinfunction "1_1") (pintype "passive"))
    )
    (net (code "36") (name "/Fillin") (class "Default")
      (node (ref "R153") (pin "1") (pinfunction "1_1") (pintype "passive"))
    )
    (net (code "37") (name "/Finger") (class "Default")
      (node (ref "R162") (pin "1") (pinfunction "1_1") (pintype "passive"))
    )
    (net (code "38") (name "/G5#") (class "Default")
      (node (ref "R105") (pin "1") (pinfunction "1_1") (pintype "passive"))
    )
    (net (code "39") (name "/G6") (class "Default")
      (node (ref "R116") (pin "1") (pinfunction "1_1") (pintype "passive"))
    )
    (net (code "40") (name "/G6#") (class "Default")
      (node (ref "R117") (pin "1") (pinfunction "1_1") (pintype "passive"))
    )
    (net (code "41") (name "/G7") (class "Default")
      (node (ref "R128") (pin "1") (pinfunction "1_1") (pintype "passive"))
    )
    (net (code "42") (name "/G7#") (class "Default")
      (node (ref "R129") (pin "1") (pinfunction "1_1") (pintype "passive"))
    )
    (net (code "43") (name "/Learn") (class "Default")
      (node (ref "R167") (pin "1") (pinfunction "1_1") (pintype "passive"))
    )
    (net (code "44") (name "/RHY1") (class "Default")
      (node (ref "R145") (pin "1") (pinfunction "1_1") (pintype "passive"))
    )
    (net (code "45") (name "/RHY2") (class "Default")
      (node (ref "R146") (pin "1") (pinfunction "1_1") (pintype "passive"))
    )
    (net (code "46") (name "/RHY3") (class "Default")
      (node (ref "R142") (pin "1") (pinfunction "1_1") (pintype "passive"))
    )
    (net (code "47") (name "/RHY4") (class "Default")
      (node (ref "R141") (pin "1") (pinfunction "1_1") (pintype "passive"))
    )
    (net (code "48") (name "/RHY5") (class "Default")
      (node (ref "R149") (pin "1") (pinfunction "1_1") (pintype "passive"))
    )
    (net (code "49") (name "/RHY6") (class "Default")
      (node (ref "R150") (pin "1") (pinfunction "1_1") (pintype "passive"))
    )
    (net (code "50") (name "/RHY7") (class "Default")
      (node (ref "R151") (pin "1") (pinfunction "1_1") (pintype "passive"))
    )
    (net (code "51") (name "/RHY8") (class "Default")
      (node (ref "R152") (pin "1") (pinfunction "1_1") (pintype "passive"))
    )
    (net (code "52") (name "/RHY9") (class "Default")
      (node (ref "R147") (pin "1") (pinfunction "1_1") (pintype "passive"))
    )
    (net (code "53") (name "/RHY10") (class "Default")
      (node (ref "R148") (pin "1") (pinfunction "1_1") (pintype "passive"))
    )
    (net (code "54") (name "/Record") (class "Default")
      (node (ref "R134") (pin "1") (pinfunction "1_1") (pintype "passive"))
    )
    (net (code "55") (name "/Replay") (class "Default")
      (node (ref "R155") (pin "1") (pinfunction "1_1") (pintype "passive"))
    )
    (net (code "56") (name "/Rhy_edit") (class "Default")
      (node (ref "R160") (pin "1") (pinfunction "1_1") (pintype "passive"))
    )
    (net (code "57") (name "/STOP") (class "Default")
      (node (ref "R156") (pin "1") (pinfunction "1_1") (pintype "passive"))
    )
    (net (code "58") (name "/Single") (class "Default")
      (node (ref "R161") (pin "1") (pinfunction "1_1") (pintype "passive"))
    )
    (net (code "59") (name "/TONE1") (class "Default")
      (node (ref "R136") (pin "1") (pinfunction "1_1") (pintype "passive"))
    )
    (net (code "60") (name "/TONE2") (class "Default")
      (node (ref "R135") (pin "1") (pinfunction "1_1") (pintype "passive"))
    )
    (net (code "61") (name "/Tempo+") (class "Default")
      (node (ref "R163") (pin "1") (pinfunction "1_1") (pintype "passive"))
    )
    (net (code "62") (name "/Tempo-") (class "Default")
      (node (ref "R164") (pin "1") (pinfunction "1_1") (pintype "passive"))
    )
    (net (code "63") (name "/VOL+") (class "Default")
      (node (ref "R165") (pin "1") (pinfunction "1_1") (pintype "passive"))
    )
    (net (code "64") (name "/VOL-") (class "Default")
      (node (ref "R166") (pin "1") (pinfunction "1_1") (pintype "passive"))
    )
    (net (code "65") (name "GND") (class "Default")
      (node (ref "P21") (pin "2") (pinfunction "2_2") (pintype "passive"))
      (node (ref "P22") (pin "2") (pinfunction "2_2") (pintype "passive"))
      (node (ref "P23") (pin "2") (pinfunction "2_2") (pintype "passive"))
      (node (ref "P24") (pin "2") (pinfunction "2_2") (pintype "passive"))
      (node (ref "P25") (pin "2") (pinfunction "2_2") (pintype "passive"))
      (node (ref "P26") (pin "2") (pinfunction "2_2") (pintype "passive"))
      (node (ref "P27") (pin "2") (pinfunction "2_2") (pintype "passive"))
      (node (ref "P28") (pin "2") (pinfunction "2_2") (pintype "passive"))
      (node (ref "P29") (pin "2") (pinfunction "2_2") (pintype "passive"))
      (node (ref "P30") (pin "2") (pinfunction "2_2") (pintype "passive"))
      (node (ref "P31") (pin "2") (pinfunction "2_2") (pintype "passive"))
      (node (ref "P32") (pin "2") (pinfunction "2_2") (pintype "passive"))
      (node (ref "P33") (pin "2") (pinfunction "2_2") (pintype "passive"))
      (node (ref "P34") (pin "2") (pinfunction "2_2") (pintype "passive"))
      (node (ref "P35") (pin "2") (pinfunction "2_2") (pintype "passive"))
      (node (ref "P36") (pin "2") (pinfunction "2_2") (pintype "passive"))
      (node (ref "P37") (pin "2") (pinfunction "2_2") (pintype "passive"))
      (node (ref "P38") (pin "2") (pinfunction "2_2") (pintype "passive"))
      (node (ref "P39") (pin "2") (pinfunction "2_2") (pintype "passive"))
      (node (ref "P40") (pin "2") (pinfunction "2_2") (pintype "passive"))
      (node (ref "P41") (pin "2") (pinfunction "2_2") (pintype "passive"))
      (node (ref "P42") (pin "2") (pinfunction "2_2") (pintype "passive"))
      (node (ref "P43") (pin "2") (pinfunction "2_2") (pintype "passive"))
      (node (ref "P44") (pin "2") (pinfunction "2_2") (pintype "passive"))
      (node (ref "P45") (pin "2") (pinfunction "2_2") (pintype "passive"))
      (node (ref "P46") (pin "2") (pinfunction "2_2") (pintype "passive"))
      (node (ref "P47") (pin "2") (pinfunction "2_2") (pintype "passive"))
      (node (ref "P48") (pin "2") (pinfunction "2_2") (pintype "passive"))
      (node (ref "P49") (pin "2") (pinfunction "2_2") (pintype "passive"))
      (node (ref "P50") (pin "2") (pinfunction "2_2") (pintype "passive"))
      (node (ref "P51") (pin "2") (pinfunction "2_2") (pintype "passive"))
      (node (ref "P52") (pin "2") (pinfunction "2_2") (pintype "passive"))
      (node (ref "P53") (pin "2") (pinfunction "2_2") (pintype "passive"))
      (node (ref "P54") (pin "2") (pinfunction "2_2") (pintype "passive"))
      (node (ref "P55") (pin "2") (pinfunction "2_2") (pintype "passive"))
      (node (ref "P56") (pin "2") (pinfunction "2_2") (pintype "passive"))
      (node (ref "P57") (pin "2") (pinfunction "2_2") (pintype "passive"))
      (node (ref "P58") (pin "2") (pinfunction "2_2") (pintype "passive"))
      (node (ref "P59") (pin "2") (pinfunction "2_2") (pintype "passive"))
      (node (ref "P60") (pin "2") (pinfunction "2_2") (pintype "passive"))
      (node (ref "P61") (pin "2") (pinfunction "2_2") (pintype "passive"))
      (node (ref "P62") (pin "2") (pinfunction "2_2") (pintype "passive"))
      (node (ref "P63") (pin "2") (pinfunction "2_2") (pintype "passive"))
      (node (ref "P64") (pin "2") (pinfunction "2_2") (pintype "passive"))
      (node (ref "P65") (pin "2") (pinfunction "2_2") (pintype "passive"))
      (node (ref "P66") (pin "2") (pinfunction "2_2") (pintype "passive"))
      (node (ref "P67") (pin "2") (pinfunction "2_2") (pintype "passive"))
      (node (ref "P68") (pin "2") (pinfunction "2_2") (pintype "passive"))
      (node (ref "P69") (pin "2") (pinfunction "2_2") (pintype "passive"))
      (node (ref "P70") (pin "2") (pinfunction "2_2") (pintype "passive"))
      (node (ref "P71") (pin "2") (pinfunction "2_2") (pintype "passive"))
      (node (ref "P72") (pin "2") (pinfunction "2_2") (pintype "passive"))
      (node (ref "P73") (pin "2") (pinfunction "2_2") (pintype "passive"))
      (node (ref "P74") (pin "2") (pinfunction "2_2") (pintype "passive"))
      (node (ref "P75") (pin "2") (pinfunction "2_2") (pintype "passive"))
      (node (ref "P76") (pin "2") (pinfunction "2_2") (pintype "passive"))
      (node (ref "P77") (pin "2") (pinfunction "2_2") (pintype "passive"))
      (node (ref "P78") (pin "2") (pinfunction "2_2") (pintype "passive"))
      (node (ref "P79") (pin "2") (pinfunction "2_2") (pintype "passive"))
      (node (ref "P80") (pin "2") (pinfunction "2_2") (pintype "passive"))
      (node (ref "P81") (pin "2") (pinfunction "2_2") (pintype "passive"))
      (node (ref "P82") (pin "2") (pinfunction "2_2") (pintype "passive"))
      (node (ref "P83") (pin "2") (pinfunction "2_2") (pintype "passive"))
      (node (ref "P84") (pin "2") (pinfunction "2_2") (pintype "passive"))
    )
    (net (code "66") (name "Net-(P21-Pad4)") (class "Default")
      (node (ref "P21") (pin "4") (pinfunction "4_4") (pintype "passive"))
      (node (ref "R105") (pin "2") (pinfunction "2_2") (pintype "passive"))
    )
    (net (code "67") (name "Net-(P22-Pad4)") (class "Default")
      (node (ref "P22") (pin "4") (pinfunction "4_4") (pintype "passive"))
      (node (ref "R106") (pin "2") (pinfunction "2_2") (pintype "passive"))
    )
    (net (code "68") (name "Net-(P23-Pad4)") (class "Default")
      (node (ref "P23") (pin "4") (pinfunction "4_4") (pintype "passive"))
      (node (ref "R107") (pin "2") (pinfunction "2_2") (pintype "passive"))
    )
    (net (code "69") (name "Net-(P24-Pad4)") (class "Default")
      (node (ref "P24") (pin "4") (pinfunction "4_4") (pintype "passive"))
      (node (ref "R108") (pin "2") (pinfunction "2_2") (pintype "passive"))
    )
    (net (code "70") (name "Net-(P25-Pad4)") (class "Default")
      (node (ref "P25") (pin "4") (pinfunction "4_4") (pintype "passive"))
      (node (ref "R109") (pin "2") (pinfunction "2_2") (pintype "passive"))
    )
    (net (code "71") (name "Net-(P26-Pad4)") (class "Default")
      (node (ref "P26") (pin "4") (pinfunction "4_4") (pintype "passive"))
      (node (ref "R110") (pin "2") (pinfunction "2_2") (pintype "passive"))
    )
    (net (code "72") (name "Net-(P27-Pad4)") (class "Default")
      (node (ref "P27") (pin "4") (pinfunction "4_4") (pintype "passive"))
      (node (ref "R111") (pin "2") (pinfunction "2_2") (pintype "passive"))
    )
    (net (code "73") (name "Net-(P28-Pad4)") (class "Default")
      (node (ref "P28") (pin "4") (pinfunction "4_4") (pintype "passive"))
      (node (ref "R112") (pin "2") (pinfunction "2_2") (pintype "passive"))
    )
    (net (code "74") (name "Net-(P29-Pad4)") (class "Default")
      (node (ref "P29") (pin "4") (pinfunction "4_4") (pintype "passive"))
      (node (ref "R113") (pin "2") (pinfunction "2_2") (pintype "passive"))
    )
    (net (code "75") (name "Net-(P30-Pad4)") (class "Default")
      (node (ref "P30") (pin "4") (pinfunction "4_4") (pintype "passive"))
      (node (ref "R114") (pin "2") (pinfunction "2_2") (pintype "passive"))
    )
    (net (code "76") (name "Net-(P31-Pad4)") (class "Default")
      (node (ref "P31") (pin "4") (pinfunction "4_4") (pintype "passive"))
      (node (ref "R115") (pin "2") (pinfunction "2_2") (pintype "passive"))
    )
    (net (code "77") (name "Net-(P32-Pad4)") (class "Default")
      (node (ref "P32") (pin "4") (pinfunction "4_4") (pintype "passive"))
      (node (ref "R116") (pin "2") (pinfunction "2_2") (pintype "passive"))
    )
    (net (code "78") (name "Net-(P33-Pad4)") (class "Default")
      (node (ref "P33") (pin "4") (pinfunction "4_4") (pintype "passive"))
      (node (ref "R117") (pin "2") (pinfunction "2_2") (pintype "passive"))
    )
    (net (code "79") (name "Net-(P34-Pad4)") (class "Default")
      (node (ref "P34") (pin "4") (pinfunction "4_4") (pintype "passive"))
      (node (ref "R118") (pin "2") (pinfunction "2_2") (pintype "passive"))
    )
    (net (code "80") (name "Net-(P35-Pad4)") (class "Default")
      (node (ref "P35") (pin "4") (pinfunction "4_4") (pintype "passive"))
      (node (ref "R119") (pin "2") (pinfunction "2_2") (pintype "passive"))
    )
    (net (code "81") (name "Net-(P36-Pad4)") (class "Default")
      (node (ref "P36") (pin "4") (pinfunction "4_4") (pintype "passive"))
      (node (ref "R120") (pin "2") (pinfunction "2_2") (pintype "passive"))
    )
    (net (code "82") (name "Net-(P37-Pad4)") (class "Default")
      (node (ref "P37") (pin "4") (pinfunction "4_4") (pintype "passive"))
      (node (ref "R121") (pin "2") (pinfunction "2_2") (pintype "passive"))
    )
    (net (code "83") (name "Net-(P38-Pad4)") (class "Default")
      (node (ref "P38") (pin "4") (pinfunction "4_4") (pintype "passive"))
      (node (ref "R122") (pin "2") (pinfunction "2_2") (pintype "passive"))
    )
    (net (code "84") (name "Net-(P39-Pad4)") (class "Default")
      (node (ref "P39") (pin "4") (pinfunction "4_4") (pintype "passive"))
      (node (ref "R123") (pin "2") (pinfunction "2_2") (pintype "passive"))
    )
    (net (code "85") (name "Net-(P40-Pad4)") (class "Default")
      (node (ref "P40") (pin "4") (pinfunction "4_4") (pintype "passive"))
      (node (ref "R124") (pin "2") (pinfunction "2_2") (pintype "passive"))
    )
    (net (code "86") (name "Net-(P41-Pad4)") (class "Default")
      (node (ref "P41") (pin "4") (pinfunction "4_4") (pintype "passive"))
      (node (ref "R125") (pin "2") (pinfunction "2_2") (pintype "passive"))
    )
    (net (code "87") (name "Net-(P42-Pad4)") (class "Default")
      (node (ref "P42") (pin "4") (pinfunction "4_4") (pintype "passive"))
      (node (ref "R126") (pin "2") (pinfunction "2_2") (pintype "passive"))
    )
    (net (code "88") (name "Net-(P43-Pad4)") (class "Default")
      (node (ref "P43") (pin "4") (pinfunction "4_4") (pintype "passive"))
      (node (ref "R127") (pin "2") (pinfunction "2_2") (pintype "passive"))
    )
    (net (code "89") (name "Net-(P44-Pad4)") (class "Default")
      (node (ref "P44") (pin "4") (pinfunction "4_4") (pintype "passive"))
      (node (ref "R128") (pin "2") (pinfunction "2_2") (pintype "passive"))
    )
    (net (code "90") (name "Net-(P45-Pad4)") (class "Default")
      (node (ref "P45") (pin "4") (pinfunction "4_4") (pintype "passive"))
      (node (ref "R129") (pin "2") (pinfunction "2_2") (pintype "passive"))
    )
    (net (code "91") (name "Net-(P46-Pad4)") (class "Default")
      (node (ref "P46") (pin "4") (pinfunction "4_4") (pintype "passive"))
      (node (ref "R130") (pin "2") (pinfunction "2_2") (pintype "passive"))
    )
    (net (code "92") (name "Net-(P47-Pad4)") (class "Default")
      (node (ref "P47") (pin "4") (pinfunction "4_4") (pintype "passive"))
      (node (ref "R131") (pin "2") (pinfunction "2_2") (pintype "passive"))
    )
    (net (code "93") (name "Net-(P48-Pad4)") (class "Default")
      (node (ref "P48") (pin "4") (pinfunction "4_4") (pintype "passive"))
      (node (ref "R132") (pin "2") (pinfunction "2_2") (pintype "passive"))
    )
    (net (code "94") (name "Net-(P49-Pad4)") (class "Default")
      (node (ref "P49") (pin "4") (pinfunction "4_4") (pintype "passive"))
      (node (ref "R133") (pin "2") (pinfunction "2_2") (pintype "passive"))
    )
    (net (code "95") (name "Net-(P50-Pad4)") (class "Default")
      (node (ref "P50") (pin "4") (pinfunction "4_4") (pintype "passive"))
      (node (ref "R134") (pin "2") (pinfunction "2_2") (pintype "passive"))
    )
    (net (code "96") (name "Net-(P51-Pad4)") (class "Default")
      (node (ref "P51") (pin "4") (pinfunction "4_4") (pintype "passive"))
      (node (ref "R135") (pin "2") (pinfunction "2_2") (pintype "passive"))
    )
    (net (code "97") (name "Net-(P52-Pad4)") (class "Default")
      (node (ref "P52") (pin "4") (pinfunction "4_4") (pintype "passive"))
      (node (ref "R136") (pin "2") (pinfunction "2_2") (pintype "passive"))
    )
    (net (code "98") (name "Net-(P53-Pad4)") (class "Default")
      (node (ref "P53") (pin "4") (pinfunction "4_4") (pintype "passive"))
      (node (ref "R137") (pin "2") (pinfunction "2_2") (pintype "passive"))
    )
    (net (code "99") (name "Net-(P54-Pad4)") (class "Default")
      (node (ref "P54") (pin "4") (pinfunction "4_4") (pintype "passive"))
      (node (ref "R138") (pin "2") (pinfunction "2_2") (pintype "passive"))
    )
    (net (code "100") (name "Net-(P55-Pad4)") (class "Default")
      (node (ref "P55") (pin "4") (pinfunction "4_4") (pintype "passive"))
      (node (ref "R139") (pin "2") (pinfunction "2_2") (pintype "passive"))
    )
    (net (code "101") (name "Net-(P56-Pad4)") (class "Default")
      (node (ref "P56") (pin "4") (pinfunction "4_4") (pintype "passive"))
      (node (ref "R140") (pin "2") (pinfunction "2_2") (pintype "passive"))
    )
    (net (code "102") (name "Net-(P57-Pad4)") (class "Default")
      (node (ref "P57") (pin "4") (pinfunction "4_4") (pintype "passive"))
      (node (ref "R141") (pin "2") (pinfunction "2_2") (pintype "passive"))
    )
    (net (code "103") (name "Net-(P58-Pad4)") (class "Default")
      (node (ref "P58") (pin "4") (pinfunction "4_4") (pintype "passive"))
      (node (ref "R142") (pin "2") (pinfunction "2_2") (pintype "passive"))
    )
    (net (code "104") (name "Net-(P59-Pad4)") (class "Default")
      (node (ref "P59") (pin "4") (pinfunction "4_4") (pintype "passive"))
      (node (ref "R143") (pin "2") (pinfunction "2_2") (pintype "passive"))
    )
    (net (code "105") (name "Net-(P60-Pad4)") (class "Default")
      (node (ref "P60") (pin "4") (pinfunction "4_4") (pintype "passive"))
      (node (ref "R144") (pin "2") (pinfunction "2_2") (pintype "passive"))
    )
    (net (code "106") (name "Net-(P61-Pad4)") (class "Default")
      (node (ref "P61") (pin "4") (pinfunction "4_4") (pintype "passive"))
      (node (ref "R145") (pin "2") (pinfunction "2_2") (pintype "passive"))
    )
    (net (code "107") (name "Net-(P62-Pad4)") (class "Default")
      (node (ref "P62") (pin "4") (pinfunction "4_4") (pintype "passive"))
      (node (ref "R146") (pin "2") (pinfunction "2_2") (pintype "passive"))
    )
    (net (code "108") (name "Net-(P63-Pad4)") (class "Default")
      (node (ref "P63") (pin "4") (pinfunction "4_4") (pintype "passive"))
      (node (ref "R147") (pin "2") (pinfunction "2_2") (pintype "passive"))
    )
    (net (code "109") (name "Net-(P64-Pad4)") (class "Default")
      (node (ref "P64") (pin "4") (pinfunction "4_4") (pintype "passive"))
      (node (ref "R148") (pin "2") (pinfunction "2_2") (pintype "passive"))
    )
    (net (code "110") (name "Net-(P65-Pad4)") (class "Default")
      (node (ref "P65") (pin "4") (pinfunction "4_4") (pintype "passive"))
      (node (ref "R149") (pin "2") (pinfunction "2_2") (pintype "passive"))
    )
    (net (code "111") (name "Net-(P66-Pad4)") (class "Default")
      (node (ref "P66") (pin "4") (pinfunction "4_4") (pintype "passive"))
      (node (ref "R150") (pin "2") (pinfunction "2_2") (pintype "passive"))
    )
    (net (code "112") (name "Net-(P67-Pad4)") (class "Default")
      (node (ref "P67") (pin "4") (pinfunction "4_4") (pintype "passive"))
      (node (ref "R151") (pin "2") (pinfunction "2_2") (pintype "passive"))
    )
    (net (code "113") (name "Net-(P68-Pad4)") (class "Default")
      (node (ref "P68") (pin "4") (pinfunction "4_4") (pintype "passive"))
      (node (ref "R152") (pin "2") (pinfunction "2_2") (pintype "passive"))
    )
    (net (code "114") (name "Net-(P69-Pad4)") (class "Default")
      (node (ref "P69") (pin "4") (pinfunction "4_4") (pintype "passive"))
      (node (ref "R153") (pin "2") (pinfunction "2_2") (pintype "passive"))
    )
    (net (code "115") (name "Net-(P70-Pad4)") (class "Default")
      (node (ref "P70") (pin "4") (pinfunction "4_4") (pintype "passive"))
      (node (ref "R154") (pin "2") (pinfunction "2_2") (pintype "passive"))
    )
    (net (code "116") (name "Net-(P71-Pad4)") (class "Default")
      (node (ref "P71") (pin "4") (pinfunction "4_4") (pintype "passive"))
      (node (ref "R155") (pin "2") (pinfunction "2_2") (pintype "passive"))
    )
    (net (code "117") (name "Net-(P72-Pad4)") (class "Default")
      (node (ref "P72") (pin "4") (pinfunction "4_4") (pintype "passive"))
      (node (ref "R156") (pin "2") (pinfunction "2_2") (pintype "passive"))
    )
    (net (code "118") (name "Net-(P73-Pad4)") (class "Default")
      (node (ref "P73") (pin "4") (pinfunction "4_4") (pintype "passive"))
      (node (ref "R157") (pin "2") (pinfunction "2_2") (pintype "passive"))
    )
    (net (code "119") (name "Net-(P74-Pad4)") (class "Default")
      (node (ref "P74") (pin "4") (pinfunction "4_4") (pintype "passive"))
      (node (ref "R158") (pin "2") (pinfunction "2_2") (pintype "passive"))
    )
    (net (code "120") (name "Net-(P75-Pad4)") (class "Default")
      (node (ref "P75") (pin "4") (pinfunction "4_4") (pintype "passive"))
      (node (ref "R159") (pin "2") (pinfunction "2_2") (pintype "passive"))
    )
    (net (code "121") (name "Net-(P76-Pad4)") (class "Default")
      (node (ref "P76") (pin "4") (pinfunction "4_4") (pintype "passive"))
      (node (ref "R160") (pin "2") (pinfunction "2_2") (pintype "passive"))
    )
    (net (code "122") (name "Net-(P77-Pad4)") (class "Default")
      (node (ref "P77") (pin "4") (pinfunction "4_4") (pintype "passive"))
      (node (ref "R161") (pin "2") (pinfunction "2_2") (pintype "passive"))
    )
    (net (code "123") (name "Net-(P78-Pad4)") (class "Default")
      (node (ref "P78") (pin "4") (pinfunction "4_4") (pintype "passive"))
      (node (ref "R162") (pin "2") (pinfunction "2_2") (pintype "passive"))
    )
    (net (code "124") (name "Net-(P79-Pad4)") (class "Default")
      (node (ref "P79") (pin "4") (pinfunction "4_4") (pintype "passive"))
      (node (ref "R163") (pin "2") (pinfunction "2_2") (pintype "passive"))
    )
    (net (code "125") (name "Net-(P80-Pad4)") (class "Default")
      (node (ref "P80") (pin "4") (pinfunction "4_4") (pintype "passive"))
      (node (ref "R164") (pin "2") (pinfunction "2_2") (pintype "passive"))
    )
    (net (code "126") (name "Net-(P81-Pad4)") (class "Default")
      (node (ref "P81") (pin "4") (pinfunction "4_4") (pintype "passive"))
      (node (ref "R165") (pin "2") (pinfunction "2_2") (pintype "passive"))
    )
    (net (code "127") (name "Net-(P82-Pad4)") (class "Default")
      (node (ref "P82") (pin "4") (pinfunction "4_4") (pintype "passive"))
      (node (ref "R166") (pin "2") (pinfunction "2_2") (pintype "passive"))
    )
    (net (code "128") (name "Net-(P83-Pad4)") (class "Default")
      (node (ref "P83") (pin "4") (pinfunction "4_4") (pintype "passive"))
      (node (ref "R167") (pin "2") (pinfunction "2_2") (pintype "passive"))
    )
    (net (code "129") (name "Net-(P84-Pad4)") (class "Default")
      (node (ref "P84") (pin "4") (pinfunction "4_4") (pintype "passive"))
      (node (ref "R168") (pin "2") (pinfunction "2_2") (pintype "passive"))
    )
    (net (code "130") (name "VCC") (class "Default")
      (node (ref "P21") (pin "1") (pinfunction "1_1") (pintype "passive"))
      (node (ref "P22") (pin "1") (pinfunction "1_1") (pintype "passive"))
      (node (ref "P23") (pin "1") (pinfunction "1_1") (pintype "passive"))
      (node (ref "P24") (pin "1") (pinfunction "1_1") (pintype "passive"))
      (node (ref "P25") (pin "1") (pinfunction "1_1") (pintype "passive"))
      (node (ref "P26") (pin "1") (pinfunction "1_1") (pintype "passive"))
      (node (ref "P27") (pin "1") (pinfunction "1_1") (pintype "passive"))
      (node (ref "P28") (pin "1") (pinfunction "1_1") (pintype "passive"))
      (node (ref "P29") (pin "1") (pinfunction "1_1") (pintype "passive"))
      (node (ref "P30") (pin "1") (pinfunction "1_1") (pintype "passive"))
      (node (ref "P31") (pin "1") (pinfunction "1_1") (pintype "passive"))
      (node (ref "P32") (pin "1") (pinfunction "1_1") (pintype "passive"))
      (node (ref "P33") (pin "1") (pinfunction "1_1") (pintype "passive"))
      (node (ref "P34") (pin "1") (pinfunction "1_1") (pintype "passive"))
      (node (ref "P35") (pin "1") (pinfunction "1_1") (pintype "passive"))
      (node (ref "P36") (pin "1") (pinfunction "1_1") (pintype "passive"))
      (node (ref "P37") (pin "1") (pinfunction "1_1") (pintype "passive"))
      (node (ref "P38") (pin "1") (pinfunction "1_1") (pintype "passive"))
      (node (ref "P39") (pin "1") (pinfunction "1_1") (pintype "passive"))
      (node (ref "P40") (pin "1") (pinfunction "1_1") (pintype "passive"))
      (node (ref "P41") (pin "1") (pinfunction "1_1") (pintype "passive"))
      (node (ref "P42") (pin "1") (pinfunction "1_1") (pintype "passive"))
      (node (ref "P43") (pin "1") (pinfunction "1_1") (pintype "passive"))
      (node (ref "P44") (pin "1") (pinfunction "1_1") (pintype "passive"))
      (node (ref "P45") (pin "1") (pinfunction "1_1") (pintype "passive"))
      (node (ref "P46") (pin "1") (pinfunction "1_1") (pintype "passive"))
      (node (ref "P47") (pin "1") (pinfunction "1_1") (pintype "passive"))
      (node (ref "P48") (pin "1") (pinfunction "1_1") (pintype "passive"))
      (node (ref "P49") (pin "1") (pinfunction "1_1") (pintype "passive"))
      (node (ref "P50") (pin "1") (pinfunction "1_1") (pintype "passive"))
      (node (ref "P51") (pin "1") (pinfunction "1_1") (pintype "passive"))
      (node (ref "P52") (pin "1") (pinfunction "1_1") (pintype "passive"))
      (node (ref "P53") (pin "1") (pinfunction "1_1") (pintype "passive"))
      (node (ref "P54") (pin "1") (pinfunction "1_1") (pintype "passive"))
      (node (ref "P55") (pin "1") (pinfunction "1_1") (pintype "passive"))
      (node (ref "P56") (pin "1") (pinfunction "1_1") (pintype "passive"))
      (node (ref "P57") (pin "1") (pinfunction "1_1") (pintype "passive"))
      (node (ref "P58") (pin "1") (pinfunction "1_1") (pintype "passive"))
      (node (ref "P59") (pin "1") (pinfunction "1_1") (pintype "passive"))
      (node (ref "P60") (pin "1") (pinfunction "1_1") (pintype "passive"))
      (node (ref "P61") (pin "1") (pinfunction "1_1") (pintype "passive"))
      (node (ref "P62") (pin "1") (pinfunction "1_1") (pintype "passive"))
      (node (ref "P63") (pin "1") (pinfunction "1_1") (pintype "passive"))
      (node (ref "P64") (pin "1") (pinfunction "1_1") (pintype "passive"))
      (node (ref "P65") (pin "1") (pinfunction "1_1") (pintype "passive"))
      (node (ref "P66") (pin "1") (pinfunction "1_1") (pintype "passive"))
      (node (ref "P67") (pin "1") (pinfunction "1_1") (pintype "passive"))
      (node (ref "P68") (pin "1") (pinfunction "1_1") (pintype "passive"))
      (node (ref "P69") (pin "1") (pinfunction "1_1") (pintype "passive"))
      (node (ref "P70") (pin "1") (pinfunction "1_1") (pintype "passive"))
      (node (ref "P71") (pin "1") (pinfunction "1_1") (pintype "passive"))
      (node (ref "P72") (pin "1") (pinfunction "1_1") (pintype "passive"))
      (node (ref "P73") (pin "1") (pinfunction "1_1") (pintype "passive"))
      (node (ref "P74") (pin "1") (pinfunction "1_1") (pintype "passive"))
      (node (ref "P75") (pin "1") (pinfunction "1_1") (pintype "passive"))
      (node (ref "P76") (pin "1") (pinfunction "1_1") (pintype "passive"))
      (node (ref "P77") (pin "1") (pinfunction "1_1") (pintype "passive"))
      (node (ref "P78") (pin "1") (pinfunction "1_1") (pintype "passive"))
      (node (ref "P79") (pin "1") (pinfunction "1_1") (pintype "passive"))
      (node (ref "P80") (pin "1") (pinfunction "1_1") (pintype "passive"))
      (node (ref "P81") (pin "1") (pinfunction "1_1") (pintype "passive"))
      (node (ref "P82") (pin "1") (pinfunction "1_1") (pintype "passive"))
      (node (ref "P83") (pin "1") (pinfunction "1_1") (pintype "passive"))
      (node (ref "P84") (pin "1") (pinfunction "1_1") (pintype "passive"))
    )
    (net (code "131") (name "unconnected-(P21-Pad3)") (class "Default")
      (node (ref "P21") (pin "3") (pinfunction "3_3") (pintype "passive"))
    )
    (net (code "132") (name "unconnected-(P22-Pad3)") (class "Default")
      (node (ref "P22") (pin "3") (pinfunction "3_3") (pintype "passive"))
    )
    (net (code "133") (name "unconnected-(P23-Pad3)") (class "Default")
      (node (ref "P23") (pin "3") (pinfunction "3_3") (pintype "passive"))
    )
    (net (code "134") (name "unconnected-(P24-Pad3)") (class "Default")
      (node (ref "P24") (pin "3") (pinfunction "3_3") (pintype "passive"))
    )
    (net (code "135") (name "unconnected-(P25-Pad3)") (class "Default")
      (node (ref "P25") (pin "3") (pinfunction "3_3") (pintype "passive"))
    )
    (net (code "136") (name "unconnected-(P26-Pad3)") (class "Default")
      (node (ref "P26") (pin "3") (pinfunction "3_3") (pintype "passive"))
    )
    (net (code "137") (name "unconnected-(P27-Pad3)") (class "Default")
      (node (ref "P27") (pin "3") (pinfunction "3_3") (pintype "passive"))
    )
    (net (code "138") (name "unconnected-(P28-Pad3)") (class "Default")
      (node (ref "P28") (pin "3") (pinfunction "3_3") (pintype "passive"))
    )
    (net (code "139") (name "unconnected-(P29-Pad3)") (class "Default")
      (node (ref "P29") (pin "3") (pinfunction "3_3") (pintype "passive"))
    )
    (net (code "140") (name "unconnected-(P30-Pad3)") (class "Default")
      (node (ref "P30") (pin "3") (pinfunction "3_3") (pintype "passive"))
    )
    (net (code "141") (name "unconnected-(P31-Pad3)") (class "Default")
      (node (ref "P31") (pin "3") (pinfunction "3_3") (pintype "passive"))
    )
    (net (code "142") (name "unconnected-(P32-Pad3)") (class "Default")
      (node (ref "P32") (pin "3") (pinfunction "3_3") (pintype "passive"))
    )
    (net (code "143") (name "unconnected-(P33-Pad3)") (class "Default")
      (node (ref "P33") (pin "3") (pinfunction "3_3") (pintype "passive"))
    )
    (net (code "144") (name "unconnected-(P34-Pad3)") (class "Default")
      (node (ref "P34") (pin "3") (pinfunction "3_3") (pintype "passive"))
    )
    (net (code "145") (name "unconnected-(P35-Pad3)") (class "Default")
      (node (ref "P35") (pin "3") (pinfunction "3_3") (pintype "passive"))
    )
    (net (code "146") (name "unconnected-(P36-Pad3)") (class "Default")
      (node (ref "P36") (pin "3") (pinfunction "3_3") (pintype "passive"))
    )
    (net (code "147") (name "unconnected-(P37-Pad3)") (class "Default")
      (node (ref "P37") (pin "3") (pinfunction "3_3") (pintype "passive"))
    )
    (net (code "148") (name "unconnected-(P38-Pad3)") (class "Default")
      (node (ref "P38") (pin "3") (pinfunction "3_3") (pintype "passive"))
    )
    (net (code "149") (name "unconnected-(P39-Pad3)") (class "Default")
      (node (ref "P39") (pin "3") (pinfunction "3_3") (pintype "passive"))
    )
    (net (code "150") (name "unconnected-(P40-Pad3)") (class "Default")
      (node (ref "P40") (pin "3") (pinfunction "3_3") (pintype "passive"))
    )
    (net (code "151") (name "unconnected-(P41-Pad3)") (class "Default")
      (node (ref "P41") (pin "3") (pinfunction "3_3") (pintype "passive"))
    )
    (net (code "152") (name "unconnected-(P42-Pad3)") (class "Default")
      (node (ref "P42") (pin "3") (pinfunction "3_3") (pintype "passive"))
    )
    (net (code "153") (name "unconnected-(P43-Pad3)") (class "Default")
      (node (ref "P43") (pin "3") (pinfunction "3_3") (pintype "passive"))
    )
    (net (code "154") (name "unconnected-(P44-Pad3)") (class "Default")
      (node (ref "P44") (pin "3") (pinfunction "3_3") (pintype "passive"))
    )
    (net (code "155") (name "unconnected-(P45-Pad3)") (class "Default")
      (node (ref "P45") (pin "3") (pinfunction "3_3") (pintype "passive"))
    )
    (net (code "156") (name "unconnected-(P46-Pad3)") (class "Default")
      (node (ref "P46") (pin "3") (pinfunction "3_3") (pintype "passive"))
    )
    (net (code "157") (name "unconnected-(P47-Pad3)") (class "Default")
      (node (ref "P47") (pin "3") (pinfunction "3_3") (pintype "passive"))
    )
    (net (code "158") (name "unconnected-(P48-Pad3)") (class "Default")
      (node (ref "P48") (pin "3") (pinfunction "3_3") (pintype "passive"))
    )
    (net (code "159") (name "unconnected-(P49-Pad3)") (class "Default")
      (node (ref "P49") (pin "3") (pinfunction "3_3") (pintype "passive"))
    )
    (net (code "160") (name "unconnected-(P50-Pad3)") (class "Default")
      (node (ref "P50") (pin "3") (pinfunction "3_3") (pintype "passive"))
    )
    (net (code "161") (name "unconnected-(P51-Pad3)") (class "Default")
      (node (ref "P51") (pin "3") (pinfunction "3_3") (pintype "passive"))
    )
    (net (code "162") (name "unconnected-(P52-Pad3)") (class "Default")
      (node (ref "P52") (pin "3") (pinfunction "3_3") (pintype "passive"))
    )
    (net (code "163") (name "unconnected-(P53-Pad3)") (class "Default")
      (node (ref "P53") (pin "3") (pinfunction "3_3") (pintype "passive"))
    )
    (net (code "164") (name "unconnected-(P54-Pad3)") (class "Default")
      (node (ref "P54") (pin "3") (pinfunction "3_3") (pintype "passive"))
    )
    (net (code "165") (name "unconnected-(P55-Pad3)") (class "Default")
      (node (ref "P55") (pin "3") (pinfunction "3_3") (pintype "passive"))
    )
    (net (code "166") (name "unconnected-(P56-Pad3)") (class "Default")
      (node (ref "P56") (pin "3") (pinfunction "3_3") (pintype "passive"))
    )
    (net (code "167") (name "unconnected-(P57-Pad3)") (class "Default")
      (node (ref "P57") (pin "3") (pinfunction "3_3") (pintype "passive"))
    )
    (net (code "168") (name "unconnected-(P58-Pad3)") (class "Default")
      (node (ref "P58") (pin "3") (pinfunction "3_3") (pintype "passive"))
    )
    (net (code "169") (name "unconnected-(P59-Pad3)") (class "Default")
      (node (ref "P59") (pin "3") (pinfunction "3_3") (pintype "passive"))
    )
    (net (code "170") (name "unconnected-(P60-Pad3)") (class "Default")
      (node (ref "P60") (pin "3") (pinfunction "3_3") (pintype "passive"))
    )
    (net (code "171") (name "unconnected-(P61-Pad3)") (class "Default")
      (node (ref "P61") (pin "3") (pinfunction "3_3") (pintype "passive"))
    )
    (net (code "172") (name "unconnected-(P62-Pad3)") (class "Default")
      (node (ref "P62") (pin "3") (pinfunction "3_3") (pintype "passive"))
    )
    (net (code "173") (name "unconnected-(P63-Pad3)") (class "Default")
      (node (ref "P63") (pin "3") (pinfunction "3_3") (pintype "passive"))
    )
    (net (code "174") (name "unconnected-(P64-Pad3)") (class "Default")
      (node (ref "P64") (pin "3") (pinfunction "3_3") (pintype "passive"))
    )
    (net (code "175") (name "unconnected-(P65-Pad3)") (class "Default")
      (node (ref "P65") (pin "3") (pinfunction "3_3") (pintype "passive"))
    )
    (net (code "176") (name "unconnected-(P66-Pad3)") (class "Default")
      (node (ref "P66") (pin "3") (pinfunction "3_3") (pintype "passive"))
    )
    (net (code "177") (name "unconnected-(P67-Pad3)") (class "Default")
      (node (ref "P67") (pin "3") (pinfunction "3_3") (pintype "passive"))
    )
    (net (code "178") (name "unconnected-(P68-Pad3)") (class "Default")
      (node (ref "P68") (pin "3") (pinfunction "3_3") (pintype "passive"))
    )
    (net (code "179") (name "unconnected-(P69-Pad3)") (class "Default")
      (node (ref "P69") (pin "3") (pinfunction "3_3") (pintype "passive"))
    )
    (net (code "180") (name "unconnected-(P70-Pad3)") (class "Default")
      (node (ref "P70") (pin "3") (pinfunction "3_3") (pintype "passive"))
    )
    (net (code "181") (name "unconnected-(P71-Pad3)") (class "Default")
      (node (ref "P71") (pin "3") (pinfunction "3_3") (pintype "passive"))
    )
    (net (code "182") (name "unconnected-(P72-Pad3)") (class "Default")
      (node (ref "P72") (pin "3") (pinfunction "3_3") (pintype "passive"))
    )
    (net (code "183") (name "unconnected-(P73-Pad3)") (class "Default")
      (node (ref "P73") (pin "3") (pinfunction "3_3") (pintype "passive"))
    )
    (net (code "184") (name "unconnected-(P74-Pad3)") (class "Default")
      (node (ref "P74") (pin "3") (pinfunction "3_3") (pintype "passive"))
    )
    (net (code "185") (name "unconnected-(P75-Pad3)") (class "Default")
      (node (ref "P75") (pin "3") (pinfunction "3_3") (pintype "passive"))
    )
    (net (code "186") (name "unconnected-(P76-Pad3)") (class "Default")
      (node (ref "P76") (pin "3") (pinfunction "3_3") (pintype "passive"))
    )
    (net (code "187") (name "unconnected-(P77-Pad3)") (class "Default")
      (node (ref "P77") (pin "3") (pinfunction "3_3") (pintype "passive"))
    )
    (net (code "188") (name "unconnected-(P78-Pad3)") (class "Default")
      (node (ref "P78") (pin "3") (pinfunction "3_3") (pintype "passive"))
    )
    (net (code "189") (name "unconnected-(P79-Pad3)") (class "Default")
      (node (ref "P79") (pin "3") (pinfunction "3_3") (pintype "passive"))
    )
    (net (code "190") (name "unconnected-(P80-Pad3)") (class "Default")
      (node (ref "P80") (pin "3") (pinfunction "3_3") (pintype "passive"))
    )
    (net (code "191") (name "unconnected-(P81-Pad3)") (class "Default")
      (node (ref "P81") (pin "3") (pinfunction "3_3") (pintype "passive"))
    )
    (net (code "192") (name "unconnected-(P82-Pad3)") (class "Default")
      (node (ref "P82") (pin "3") (pinfunction "3_3") (pintype "passive"))
    )
    (net (code "193") (name "unconnected-(P83-Pad3)") (class "Default")
      (node (ref "P83") (pin "3") (pinfunction "3_3") (pintype "passive"))
    )
    (net (code "194") (name "unconnected-(P84-Pad3)") (class "Default")
      (node (ref "P84") (pin "3") (pinfunction "3_3") (pintype "passive"))
    )
  )
)
